# 05_Output.net
KiCad netlist of a schematic drawn in Altium Designer
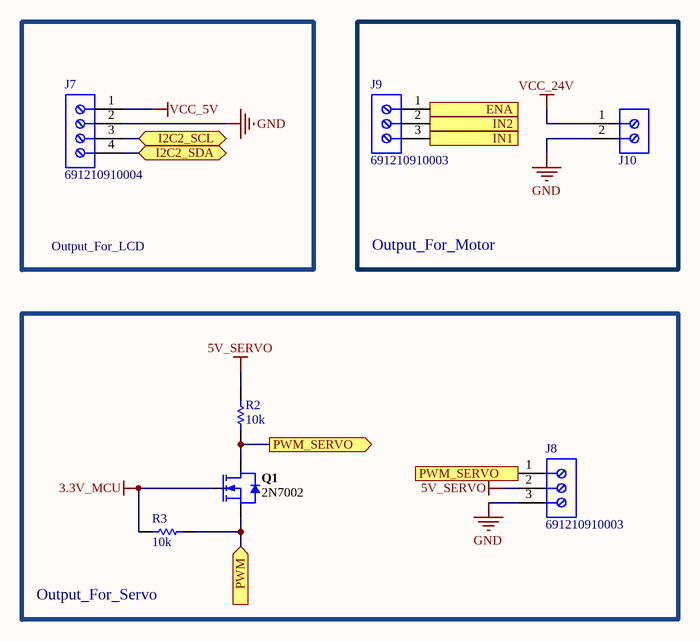
[diagram p0: 05_Output.SchDoc]

(export (version "E")
  (design (tool "Eeschema 10.0.6"))
  (components
    (comp (ref "J7")
      (value "691210910004")
      (footprint "691210910004")
      (description "WR-TBL Serie 2109 Horizontal Entry, Rising Cage Clamp, pitch 2.54mm, 4p")
      (fields (field (name "PUBLISHER") "Wurth Elektronik"))
      (libsource (lib "691322310002.") (part "691210910004"))
    )
    (comp (ref "J8")
      (value "691210910003")
      (footprint "691210910003")
      (description "WR-TBL Serie 2109 Horizontal Entry, Rising Cage Clamp, pitch 2.54mm, 3p")
      (fields (field (name "PUBLISHER") "Wurth Elektronik"))
      (libsource (lib "691322310002.") (part "691210910003"))
    )
    (comp (ref "J9")
      (value "691210910003")
      (footprint "691210910003")
      (description "WR-TBL Serie 2109 Horizontal Entry, Rising Cage Clamp, pitch 2.54mm, 3p")
      (fields (field (name "PUBLISHER") "Wurth Elektronik"))
      (libsource (lib "691322310002.") (part "691210910003"))
    )
    (comp (ref "J10")
      (value "691137710002")
      (footprint "691137710002")
      (description "WR-TBL Series 1377 Horizontal Entry, Through Hole, pitch 5mm, 2p")
      (fields (field (name "MANUFACTURER") "Wurth Elektronik"))
      (libsource (lib "Altium_WR-TBL (rev22a)") (part "691137710002"))
    )
    (comp (ref "Q1")
      (value "2N7002")
      (footprint "SOT23-123")
      (description "N-Channel 60 V 340mA (Ta) 350mW (Ta) Surface Mount SOT-23")
      (fields (field (name "MFR") "Yangzhou Yangjie Electronic Technology Co.,Ltd"))
      (libsource (lib "TechMT.VN_Lib_Project v2") (part "2N7002"))
    )
    (comp (ref "R2")
      (value "10k")
      (footprint "RES-SM-0603")
      (description "RES SMD 10K OHM 1% 1/4W 0603")
      (fields (field (name "MFR") "Rohm Semiconductor") (field (name "TOLERANCE") "±1%"))
      (libsource (lib "PIF_Library") (part "RESISTOR SMD"))
    )
    (comp (ref "R3")
      (value "10k")
      (footprint "RES-SM-0603")
      (description "RES SMD 10K OHM 1% 1/4W 0603")
      (fields (field (name "MFR") "Rohm Semiconductor") (field (name "TOLERANCE") "±1%"))
      (libsource (lib "PIF_Library") (part "RESISTOR SMD"))
    )
  )
  (nets
    (net (code "1") (name "/ENA") (class "Default")
      (node (ref "J9") (pin "1") (pinfunction "1_1") (pintype "passive"))
    )
    (net (code "2") (name "/I2C2_SCL") (class "Default")
      (node (ref "J7") (pin "3") (pinfunction "3_3") (pintype "passive"))
    )
    (net (code "3") (name "/I2C2_SDA") (class "Default")
      (node (ref "J7") (pin "4") (pinfunction "4_4") (pintype "passive"))
    )
    (net (code "4") (name "/IN1") (class "Default")
      (node (ref "J9") (pin "3") (pinfunction "3_3") (pintype "passive"))
    )
    (net (code "5") (name "/IN2") (class "Default")
      (node (ref "J9") (pin "2") (pinfunction "2_2") (pintype "passive"))
    )
    (net (code "6") (name "/PWM") (class "Default")
      (node (ref "Q1") (pin "3") (pinfunction "S_3") (pintype "passive"))
      (node (ref "R3") (pin "2") (pinfunction "2_2") (pintype "passive"))
    )
    (net (code "7") (name "/PWM_SERVO") (class "Default")
      (node (ref "J8") (pin "1") (pinfunction "1_1") (pintype "passive"))
      (node (ref "Q1") (pin "2") (pinfunction "D_2") (pintype "passive"))
      (node (ref "R2") (pin "1") (pinfunction "1_1") (pintype "passive"))
    )
    (net (code "8") (name "3.3V_MCU") (class "Default")
      (node (ref "Q1") (pin "1") (pinfunction "G_1") (pintype "passive"))
      (node (ref "R3") (pin "1") (pinfunction "1_1") (pintype "passive"))
    )
    (net (code "9") (name "5V_SERVO") (class "Default")
      (node (ref "J8") (pin "2") (pinfunction "2_2") (pintype "passive"))
      (node (ref "R2") (pin "2") (pinfunction "2_2") (pintype "passive"))
    )
    (net (code "10") (name "GND") (class "Default")
      (node (ref "J10") (pin "2") (pinfunction "2_2") (pintype "passive"))
      (node (ref "J7") (pin "2") (pinfunction "2_2") (pintype "passive"))
      (node (ref "J8") (pin "3") (pinfunction "3_3") (pintype "passive"))
    )
    (net (code "11") (name "VCC_5V") (class "Default")
      (node (ref "J7") (pin "1") (pinfunction "1_1") (pintype "passive"))
    )
    (net (code "12") (name "VCC_24V") (class "Default")
      (node (ref "J10") (pin "1") (pinfunction "1_1") (pintype "passive"))
    )
  )
)
